# charger_booster_reva.net
KiCad netlist of a schematic drawn in EAGLE
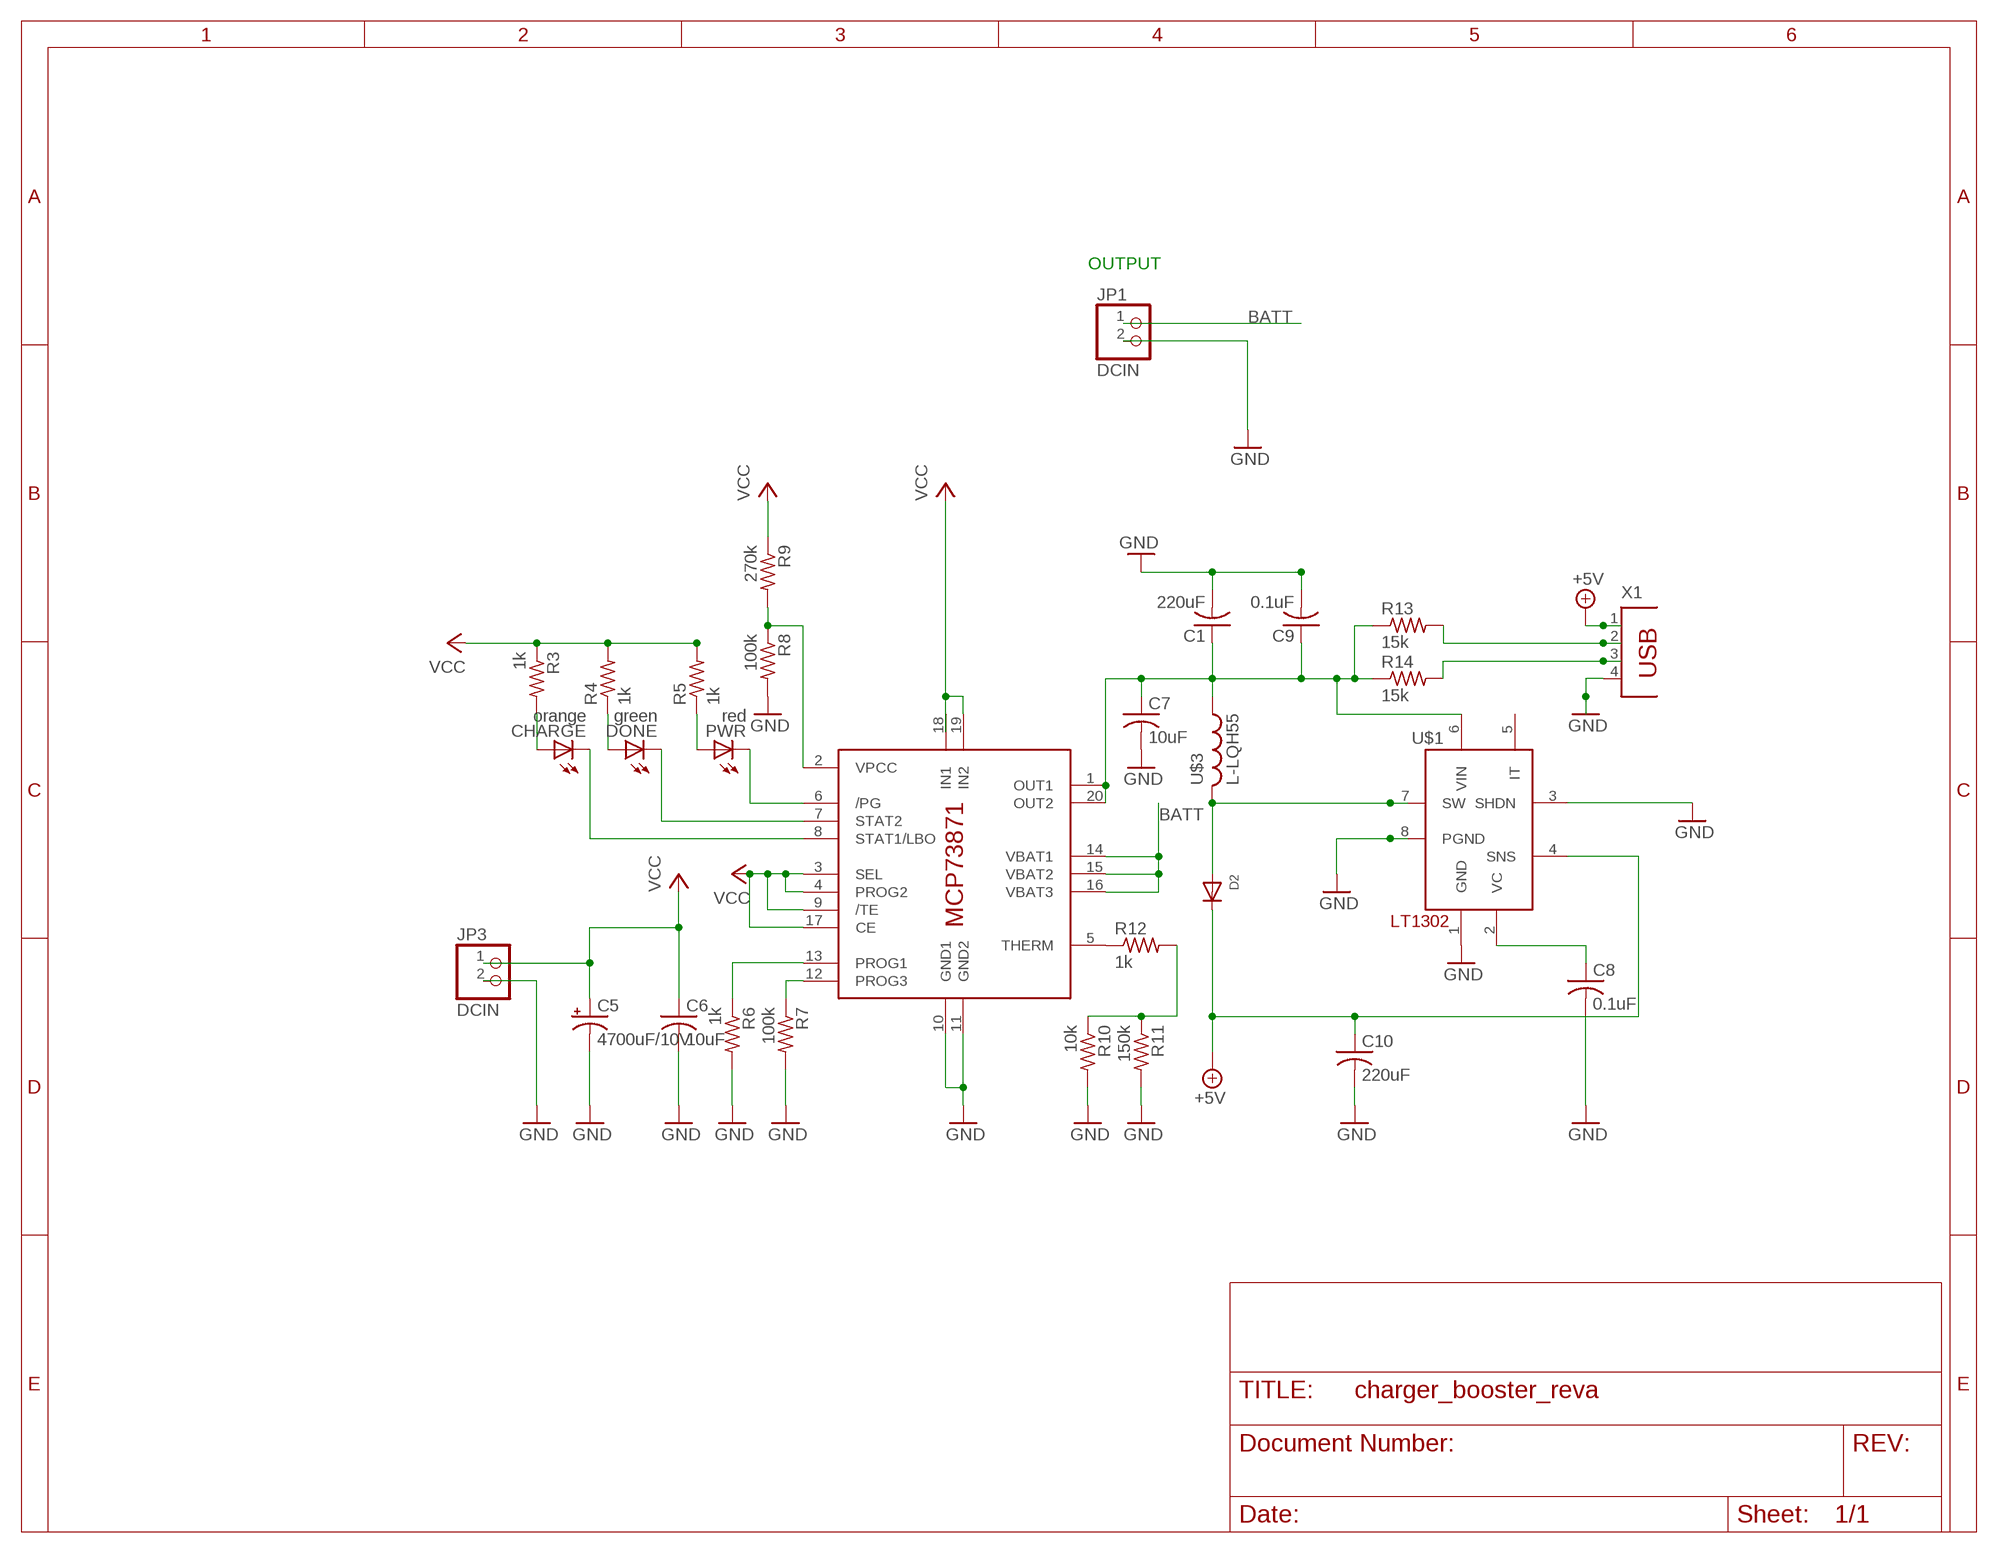
[diagram p0: schematic, sheet 1]

(export (version "E")
  (design (tool "Eeschema 10.0.6"))
  (components
    (comp (ref "C1")
      (value "220uF")
      (footprint "eagle-import:C0805K")
      (fields (field (name "MPN") "12063D106KAT2A"))
      (libsource (lib "eagle-import") (part "C-USC0805K"))
    )
    (comp (ref "C5")
      (value "4700uF/10V")
      (footprint "eagle-import:E5-13")
      (libsource (lib "eagle-import") (part "CPOL-USE5-13"))
    )
    (comp (ref "C6")
      (value "10uF")
      (footprint "eagle-import:C0805K")
      (fields (field (name "MPN") "12063D106KAT2A"))
      (libsource (lib "eagle-import") (part "C-USC0805K"))
    )
    (comp (ref "C7")
      (value "10uF")
      (footprint "eagle-import:C0805K")
      (fields (field (name "MPN") "12063D106KAT2A"))
      (libsource (lib "eagle-import") (part "C-USC0805K"))
    )
    (comp (ref "C8")
      (value "0.1uF")
      (footprint "eagle-import:C0805K")
      (fields (field (name "MPN") "12063D106KAT2A"))
      (libsource (lib "eagle-import") (part "C-USC0805K"))
    )
    (comp (ref "C9")
      (value "0.1uF")
      (footprint "eagle-import:C050-024X044")
      (fields (field (name "MPN") "0402ZD104KAT2A"))
      (libsource (lib "eagle-import") (part "C-US050-024X044"))
    )
    (comp (ref "C10")
      (value "220uF")
      (footprint "eagle-import:C0805K")
      (fields (field (name "MPN") "12063D106KAT2A"))
      (libsource (lib "eagle-import") (part "C-USC0805K"))
    )
    (comp (ref "CHARGE")
      (value "orange")
      (footprint "eagle-import:CHIPLED_0805")
      (libsource (lib "eagle-import") (part "LEDCHIPLED_0805"))
    )
    (comp (ref "D2")
      (value "DIODESOD-523")
      (footprint "eagle-import:SOD-523")
      (libsource (lib "eagle-import") (part "DIODESOD-523"))
    )
    (comp (ref "DONE")
      (value "green")
      (footprint "eagle-import:CHIPLED_0805")
      (fields (field (name "MPN") "150080GS75000"))
      (libsource (lib "eagle-import") (part "LEDCHIPLED_0805"))
    )
    (comp (ref "IC1")
      (value "MCP73871")
      (footprint "eagle-import:QFN20")
      (fields (field (name "MPN") "MCP73871-2CAI/ML"))
      (libsource (lib "eagle-import") (part "MCP73871"))
    )
    (comp (ref "JP1")
      (value "DCIN")
      (footprint "eagle-import:1X02")
      (libsource (lib "eagle-import") (part "PINHD-1X2"))
    )
    (comp (ref "JP3")
      (value "DCIN")
      (footprint "eagle-import:1X02")
      (libsource (lib "eagle-import") (part "PINHD-1X2"))
    )
    (comp (ref "PWR")
      (value "red")
      (footprint "eagle-import:CHIPLED_0805")
      (fields (field (name "MPN") "150080RS75000"))
      (libsource (lib "eagle-import") (part "LEDCHIPLED_0805"))
    )
    (comp (ref "R3")
      (value "1k")
      (footprint "eagle-import:R0805")
      (fields (field (name "MF") "FARNELL") (field (name "MPN") "MCF 0.25W 1K"))
      (libsource (lib "eagle-import") (part "R-US_R0805"))
    )
    (comp (ref "R4")
      (value "1k")
      (footprint "eagle-import:R0805")
      (fields (field (name "MF") "FARNELL") (field (name "MPN") "MCF 0.25W 1K"))
      (libsource (lib "eagle-import") (part "R-US_R0805"))
    )
    (comp (ref "R5")
      (value "1k")
      (footprint "eagle-import:R0805")
      (fields (field (name "MF") "FARNELL") (field (name "MPN") "MCF 0.25W 1K"))
      (libsource (lib "eagle-import") (part "R-US_R0805"))
    )
    (comp (ref "R6")
      (value "1k")
      (footprint "eagle-import:R0805")
      (fields (field (name "MF") "FARNELL") (field (name "MPN") "MCF 0.25W 1K"))
      (libsource (lib "eagle-import") (part "R-US_R0805"))
    )
    (comp (ref "R7")
      (value "100k")
      (footprint "eagle-import:R0805")
      (fields (field (name "MF") "FARNELL") (field (name "MPN") "MCF 0.25W 100K"))
      (libsource (lib "eagle-import") (part "R-US_R0805"))
    )
    (comp (ref "R8")
      (value "100k")
      (footprint "eagle-import:R0805")
      (fields (field (name "MF") "FARNELL") (field (name "MPN") "MCF 0.25W 100K"))
      (libsource (lib "eagle-import") (part "R-US_R0805"))
    )
    (comp (ref "R9")
      (value "270k")
      (footprint "eagle-import:R0805")
      (fields (field (name "MF") "AVX CORPORATION") (field (name "MPN") "08055A270KAT2A"))
      (libsource (lib "eagle-import") (part "R-US_R0805"))
    )
    (comp (ref "R10")
      (value "10k")
      (footprint "eagle-import:R0805")
      (fields (field (name "MPN") "MCHP05W4F1002T5E"))
      (libsource (lib "eagle-import") (part "R-US_R0805"))
    )
    (comp (ref "R11")
      (value "150k")
      (footprint "eagle-import:R0805")
      (fields (field (name "MPN") "MCHP05W4F1503T5E"))
      (libsource (lib "eagle-import") (part "R-US_R0805"))
    )
    (comp (ref "R12")
      (value "1k")
      (footprint "eagle-import:R0805")
      (fields (field (name "MF") "FARNELL") (field (name "MPN") "MCF 0.25W 1K"))
      (libsource (lib "eagle-import") (part "R-US_R0805"))
    )
    (comp (ref "R13")
      (value "15k")
      (footprint "eagle-import:R0805")
      (libsource (lib "eagle-import") (part "R-US_R0805"))
    )
    (comp (ref "R14")
      (value "15k")
      (footprint "eagle-import:R0805")
      (libsource (lib "eagle-import") (part "R-US_R0805"))
    )
    (comp (ref "U$1")
      (value "LT1302")
      (footprint "eagle-import:DIL08")
      (fields (field (name "MPN") "LT1302CN8-5#PBF"))
      (libsource (lib "eagle-import") (part "LT1302"))
    )
    (comp (ref "U$3")
      (value "L-LQH55")
      (footprint "eagle-import:LQH55")
      (libsource (lib "eagle-import") (part "L-LQH55"))
    )
    (comp (ref "X1")
      (value "PN87520")
      (footprint "eagle-import:PN87520")
      (libsource (lib "eagle-import") (part "PN87520"))
    )
  )
  (nets
    (net (code "1") (name "+5V") (class "Default")
      (node (ref "C10") (pin "1") (pinfunction "1_1") (pintype "passive"))
      (node (ref "D2") (pin "K") (pinfunction "C_K") (pintype "passive"))
      (node (ref "U$1") (pin "4") (pinfunction "SNS_4") (pintype "passive"))
      (node (ref "X1") (pin "1") (pinfunction "1_1") (pintype "passive"))
    )
    (net (code "2") (name "/BATT") (class "Default")
      (node (ref "IC1") (pin "14") (pinfunction "VBAT1_14") (pintype "output"))
      (node (ref "IC1") (pin "15") (pinfunction "VBAT2_15") (pintype "output"))
      (node (ref "IC1") (pin "16") (pinfunction "VBAT3_16") (pintype "output"))
      (node (ref "JP1") (pin "1") (pinfunction "1_1") (pintype "passive"))
    )
    (net (code "3") (name "GND") (class "Default")
      (node (ref "C1") (pin "2") (pinfunction "2_2") (pintype "passive"))
      (node (ref "C10") (pin "2") (pinfunction "2_2") (pintype "passive"))
      (node (ref "C5") (pin "-") (pinfunction "-_-") (pintype "passive"))
      (node (ref "C6") (pin "2") (pinfunction "2_2") (pintype "passive"))
      (node (ref "C7") (pin "2") (pinfunction "2_2") (pintype "passive"))
      (node (ref "C8") (pin "2") (pinfunction "2_2") (pintype "passive"))
      (node (ref "C9") (pin "2") (pinfunction "2_2") (pintype "passive"))
      (node (ref "IC1") (pin "10") (pinfunction "GND1_10") (pintype "power_in"))
      (node (ref "IC1") (pin "11") (pinfunction "GND2_11") (pintype "power_in"))
      (node (ref "JP1") (pin "2") (pinfunction "2_2") (pintype "passive"))
      (node (ref "JP3") (pin "2") (pinfunction "2_2") (pintype "passive"))
      (node (ref "R10") (pin "2") (pinfunction "2_2") (pintype "passive"))
      (node (ref "R11") (pin "2") (pinfunction "2_2") (pintype "passive"))
      (node (ref "R6") (pin "2") (pinfunction "2_2") (pintype "passive"))
      (node (ref "R7") (pin "2") (pinfunction "2_2") (pintype "passive"))
      (node (ref "R8") (pin "2") (pinfunction "2_2") (pintype "passive"))
      (node (ref "U$1") (pin "1") (pinfunction "GND_1") (pintype "input"))
      (node (ref "U$1") (pin "3") (pinfunction "SHDN_3") (pintype "input"))
      (node (ref "U$1") (pin "8") (pinfunction "PGND_8") (pintype "input"))
      (node (ref "X1") (pin "4") (pinfunction "4_4") (pintype "passive"))
    )
    (net (code "4") (name "Net-(CHARGE-PadA)") (class "Default")
      (node (ref "CHARGE") (pin "A") (pinfunction "A_A") (pintype "passive"))
      (node (ref "R3") (pin "2") (pinfunction "2_2") (pintype "passive"))
    )
    (net (code "5") (name "Net-(DONE-PadA)") (class "Default")
      (node (ref "DONE") (pin "A") (pinfunction "A_A") (pintype "passive"))
      (node (ref "R4") (pin "1") (pinfunction "1_1") (pintype "passive"))
    )
    (net (code "6") (name "Net-(IC1-OUT1)") (class "Default")
      (node (ref "C1") (pin "1") (pinfunction "1_1") (pintype "passive"))
      (node (ref "C7") (pin "1") (pinfunction "1_1") (pintype "passive"))
      (node (ref "C9") (pin "1") (pinfunction "1_1") (pintype "passive"))
      (node (ref "IC1") (pin "1") (pinfunction "OUT1_1") (pintype "output"))
      (node (ref "IC1") (pin "20") (pinfunction "OUT2_20") (pintype "output"))
      (node (ref "R13") (pin "1") (pinfunction "1_1") (pintype "passive"))
      (node (ref "R14") (pin "1") (pinfunction "1_1") (pintype "passive"))
      (node (ref "U$1") (pin "6") (pinfunction "VIN_6") (pintype "input"))
      (node (ref "U$3") (pin "1") (pinfunction "1_1") (pintype "passive"))
    )
    (net (code "7") (name "Net-(IC1-PROG1)") (class "Default")
      (node (ref "IC1") (pin "13") (pinfunction "PROG1_13") (pintype "input"))
      (node (ref "R6") (pin "1") (pinfunction "1_1") (pintype "passive"))
    )
    (net (code "8") (name "Net-(IC1-PROG3)") (class "Default")
      (node (ref "IC1") (pin "12") (pinfunction "PROG3_12") (pintype "input"))
      (node (ref "R7") (pin "1") (pinfunction "1_1") (pintype "passive"))
    )
    (net (code "9") (name "Net-(IC1-STAT1{slash}LBO)") (class "Default")
      (node (ref "CHARGE") (pin "C") (pinfunction "C_C") (pintype "passive"))
      (node (ref "IC1") (pin "8") (pinfunction "STAT1/LBO_8") (pintype "output"))
    )
    (net (code "10") (name "Net-(IC1-STAT2)") (class "Default")
      (node (ref "DONE") (pin "C") (pinfunction "C_C") (pintype "passive"))
      (node (ref "IC1") (pin "7") (pinfunction "STAT2_7") (pintype "output"))
    )
    (net (code "11") (name "Net-(IC1-THERM)") (class "Default")
      (node (ref "IC1") (pin "5") (pinfunction "THERM_5") (pintype "input"))
      (node (ref "R12") (pin "1") (pinfunction "1_1") (pintype "passive"))
    )
    (net (code "12") (name "Net-(IC1-VPCC)") (class "Default")
      (node (ref "IC1") (pin "2") (pinfunction "VPCC_2") (pintype "input"))
      (node (ref "R8") (pin "1") (pinfunction "1_1") (pintype "passive"))
      (node (ref "R9") (pin "2") (pinfunction "2_2") (pintype "passive"))
    )
    (net (code "13") (name "Net-(IC1-{slash}PG)") (class "Default")
      (node (ref "IC1") (pin "6") (pinfunction "/PG_6") (pintype "output"))
      (node (ref "PWR") (pin "C") (pinfunction "C_C") (pintype "passive"))
    )
    (net (code "14") (name "Net-(PWR-PadA)") (class "Default")
      (node (ref "PWR") (pin "A") (pinfunction "A_A") (pintype "passive"))
      (node (ref "R5") (pin "1") (pinfunction "1_1") (pintype "passive"))
    )
    (net (code "15") (name "Net-(R10-Pad1)") (class "Default")
      (node (ref "R10") (pin "1") (pinfunction "1_1") (pintype "passive"))
      (node (ref "R11") (pin "1") (pinfunction "1_1") (pintype "passive"))
      (node (ref "R12") (pin "2") (pinfunction "2_2") (pintype "passive"))
    )
    (net (code "16") (name "Net-(R13-Pad2)") (class "Default")
      (node (ref "R13") (pin "2") (pinfunction "2_2") (pintype "passive"))
      (node (ref "X1") (pin "2") (pinfunction "2_2") (pintype "passive"))
    )
    (net (code "17") (name "Net-(R14-Pad2)") (class "Default")
      (node (ref "R14") (pin "2") (pinfunction "2_2") (pintype "passive"))
      (node (ref "X1") (pin "3") (pinfunction "3_3") (pintype "passive"))
    )
    (net (code "18") (name "Net-(U$1-SW)") (class "Default")
      (node (ref "D2") (pin "A") (pinfunction "A_A") (pintype "passive"))
      (node (ref "U$1") (pin "7") (pinfunction "SW_7") (pintype "input"))
      (node (ref "U$3") (pin "2") (pinfunction "2_2") (pintype "passive"))
    )
    (net (code "19") (name "Net-(U$1-VC)") (class "Default")
      (node (ref "C8") (pin "1") (pinfunction "1_1") (pintype "passive"))
      (node (ref "U$1") (pin "2") (pinfunction "VC_2") (pintype "passive"))
    )
    (net (code "20") (name "VCC") (class "Default")
      (node (ref "C5") (pin "+") (pinfunction "+_+") (pintype "passive"))
      (node (ref "C6") (pin "1") (pinfunction "1_1") (pintype "passive"))
      (node (ref "IC1") (pin "17") (pinfunction "CE_17") (pintype "input"))
      (node (ref "IC1") (pin "19") (pinfunction "IN2_19") (pintype "input"))
      (node (ref "IC1") (pin "3") (pinfunction "SEL_3") (pintype "input"))
      (node (ref "IC1") (pin "4") (pinfunction "PROG2_4") (pintype "input"))
      (node (ref "IC1") (pin "9") (pinfunction "/TE_9") (pintype "input"))
      (node (ref "JP3") (pin "1") (pinfunction "1_1") (pintype "passive"))
      (node (ref "R3") (pin "1") (pinfunction "1_1") (pintype "passive"))
      (node (ref "R4") (pin "2") (pinfunction "2_2") (pintype "passive"))
      (node (ref "R5") (pin "2") (pinfunction "2_2") (pintype "passive"))
      (node (ref "R9") (pin "1") (pinfunction "1_1") (pintype "passive"))
    )
    (net (code "21") (name "unconnected-(IC1-IN1-Pad18)") (class "Default")
      (node (ref "IC1") (pin "18") (pinfunction "IN1_18") (pintype "input"))
    )
    (net (code "22") (name "unconnected-(U$1-IT-Pad5)") (class "Default")
      (node (ref "U$1") (pin "5") (pinfunction "IT_5") (pintype "input"))
    )
  )
)
